# exhaust_gas_temp_oxy.net
KiCad netlist of a schematic drawn in Altium Designer
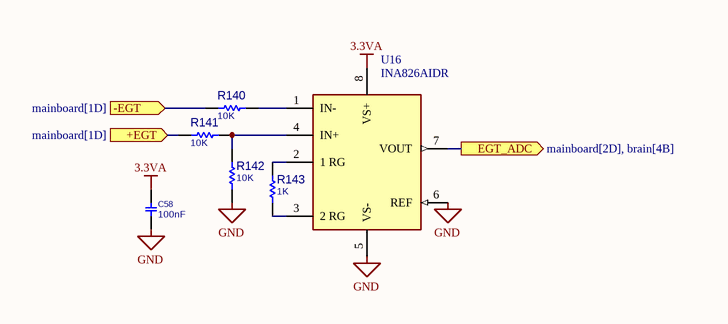
[diagram p0: exhaust_gas_temp_oxy.SchDoc]

(export (version "E")
  (design (tool "Eeschema 10.0.6"))
  (components
    (comp (ref "C58")
      (value "100nF")
      (footprint "C0805")
      (description "CAP, MLCC")
      (fields (field (name "MANF_P#") "MANF_PART#"))
      (libsource (lib "passive_smd") (part "CAP_SMD_MLCC_0805"))
    )
    (comp (ref "R140")
      (value "10K")
      (footprint "R1206")
      (description "RESISTOR, SMD")
      (libsource (lib "passive_smd") (part "RES_SMD_1206"))
    )
    (comp (ref "R141")
      (value "10K")
      (footprint "R1206")
      (description "RESISTOR, SMD")
      (libsource (lib "passive_smd") (part "RES_SMD_1206"))
    )
    (comp (ref "R142")
      (value "10K")
      (footprint "R1206")
      (description "RESISTOR, SMD")
      (libsource (lib "passive_smd") (part "RES_SMD_1206"))
    )
    (comp (ref "R143")
      (value "1K")
      (footprint "R1206")
      (description "RESISTOR, SMD")
      (libsource (lib "passive_smd") (part "RES_SMD_1206"))
    )
    (comp (ref "U16")
      (value "INA826AIDR")
      (footprint "SOIC-8")
      (description "IC INST AMP 1 CIRCUIT 8SOIC")
      (libsource (lib "alib") (part "INA826"))
    )
  )
  (nets
    (net (code "1") (name "/+EGT") (class "Default")
      (node (ref "R141") (pin "1") (pinfunction "1_1") (pintype "passive"))
    )
    (net (code "2") (name "/-EGT") (class "Default")
      (node (ref "R140") (pin "2") (pinfunction "2_2") (pintype "passive"))
    )
    (net (code "3") (name "/EGT_ADC") (class "Default")
      (node (ref "U16") (pin "7") (pinfunction "VOUT_7") (pintype "output"))
    )
    (net (code "4") (name "3.3VA") (class "Default")
      (node (ref "C58") (pin "2") (pinfunction "2_2") (pintype "passive"))
      (node (ref "U16") (pin "8") (pinfunction "VS+_8") (pintype "power_in"))
    )
    (net (code "5") (name "GND") (class "Default")
      (node (ref "C58") (pin "1") (pinfunction "1_1") (pintype "passive"))
      (node (ref "R142") (pin "1") (pinfunction "1_1") (pintype "passive"))
      (node (ref "U16") (pin "5") (pinfunction "VS-_5") (pintype "power_in"))
      (node (ref "U16") (pin "6") (pinfunction "REF_6") (pintype "input"))
    )
    (net (code "6") (name "Net-(U16-1_RG)") (class "Default")
      (node (ref "R143") (pin "2") (pinfunction "2_2") (pintype "passive"))
      (node (ref "U16") (pin "2") (pinfunction "1_RG_2") (pintype "passive"))
    )
    (net (code "7") (name "Net-(U16-2_RG)") (class "Default")
      (node (ref "R143") (pin "1") (pinfunction "1_1") (pintype "passive"))
      (node (ref "U16") (pin "3") (pinfunction "2_RG_3") (pintype "passive"))
    )
    (net (code "8") (name "Net-(U16-IN+)") (class "Default")
      (node (ref "R141") (pin "2") (pinfunction "2_2") (pintype "passive"))
      (node (ref "R142") (pin "2") (pinfunction "2_2") (pintype "passive"))
      (node (ref "U16") (pin "4") (pinfunction "IN+_4") (pintype "passive"))
    )
    (net (code "9") (name "Net-(U16-IN-)") (class "Default")
      (node (ref "R140") (pin "1") (pinfunction "1_1") (pintype "passive"))
      (node (ref "U16") (pin "1") (pinfunction "IN-_1") (pintype "power_in"))
    )
  )
)
